# mcu0_primary.net
KiCad netlist of a schematic drawn in Altium Designer
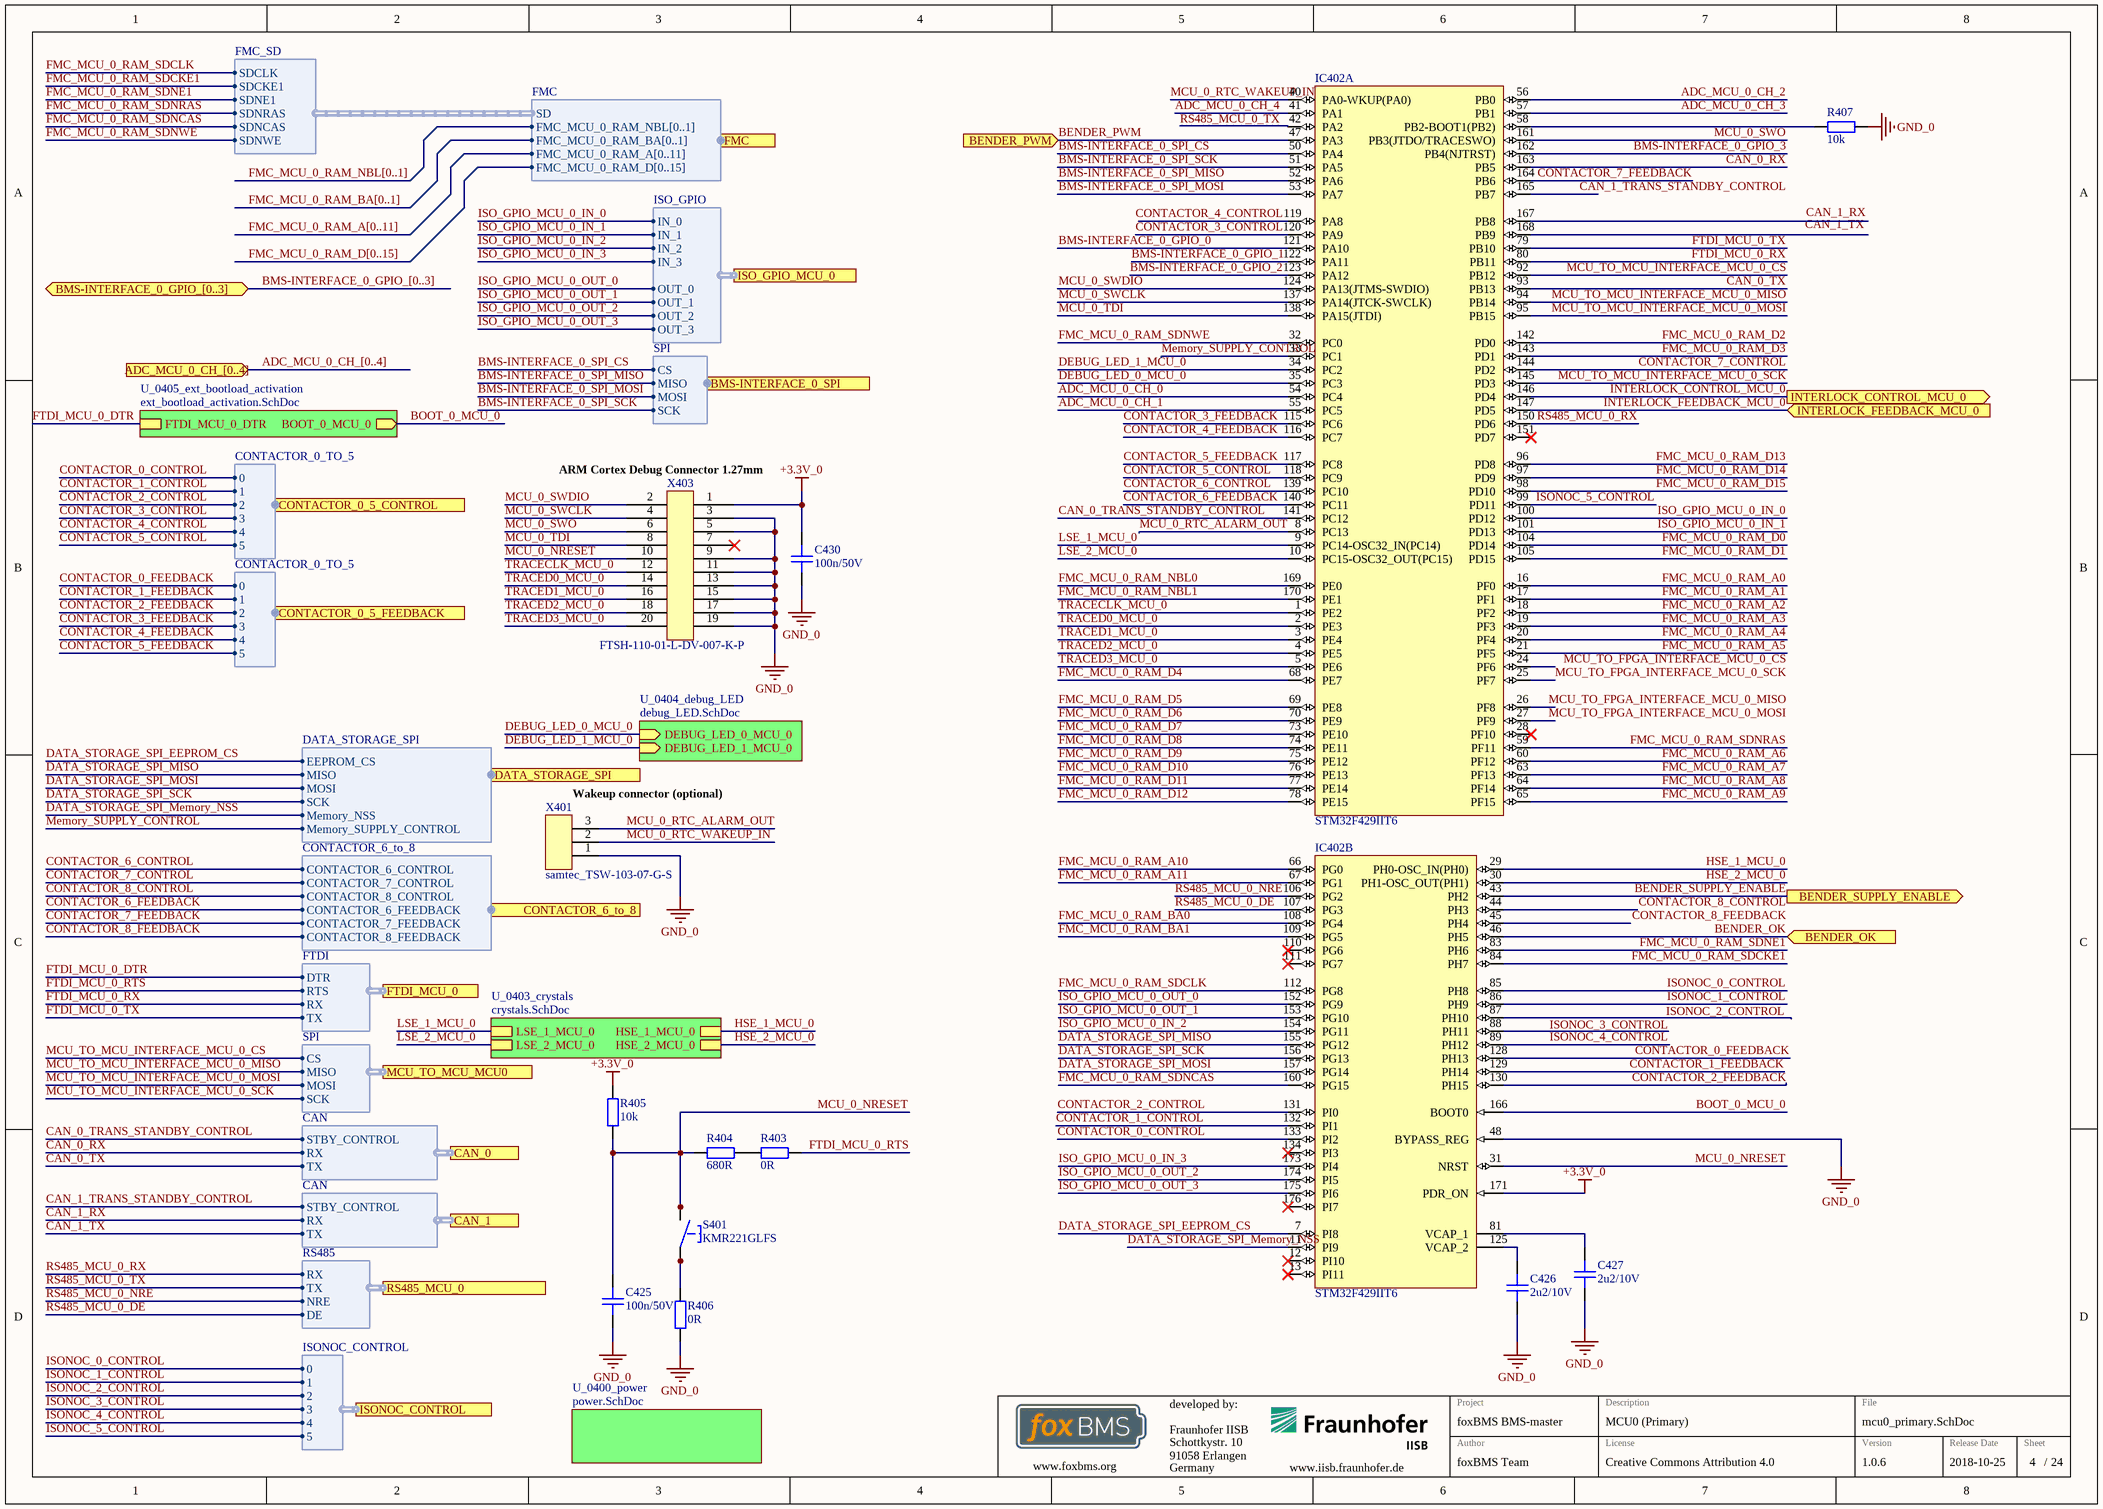
[diagram p0: mcu0_primary.SchDoc]

(export (version "E")
  (design (tool "Eeschema 10.0.6"))
  (components
    (comp (ref "C425")
      (value "100n/50V")
      (footprint "CAPC1608X08N")
      (description "MLCC")
      (fields (field (name "PART NUMBER") "gen_C_ceramic_100n_50V_X7R_0603"))
      (libsource (lib "OE750") (part "C"))
    )
    (comp (ref "C426")
      (value "2u2/10V")
      (footprint "CAPC1608X08N")
      (description "MLCC")
      (fields (field (name "PART NUMBER") "gen_C_ceramic_2u2_10V_X5R_0603"))
      (libsource (lib "OE750") (part "C"))
    )
    (comp (ref "C427")
      (value "2u2/10V")
      (footprint "CAPC1608X08N")
      (description "MLCC")
      (fields (field (name "PART NUMBER") "gen_C_ceramic_2u2_10V_X5R_0603"))
      (libsource (lib "OE750") (part "C"))
    )
    (comp (ref "C430")
      (value "100n/50V")
      (footprint "CAPC1608X08N")
      (description "MLCC")
      (fields (field (name "PART NUMBER") "gen_C_ceramic_100n_50V_X7R_0603"))
      (libsource (lib "OE750") (part "C"))
    )
    (comp (ref "IC402")
      (value "STM32F429IIT6")
      (footprint "STM-LQFP176_N")
      (fields (field (name "MANUFACTURER") "STMicroelectronics"))
      (libsource (lib "Altium Content Vault") (part "MC-ARM-STM32F4X9-SQ176"))
    )
    (comp (ref "R403")
      (value "0R")
      (footprint "RESC1608X05N")
      (description "SMD Resistor 0R 0603")
      (fields (field (name "PART NUMBER") "gen_R_0R_0603") (field (name "POWER") "0.1W"))
      (libsource (lib "OE750") (part "R"))
    )
    (comp (ref "R404")
      (value "680R")
      (footprint "RESC1608X05N")
      (description "SMD Resistor 680R 0603")
      (fields (field (name "PART NUMBER") "gen_R_680R_0603") (field (name "TOLERANCE") "1%"))
      (libsource (lib "OE750") (part "R"))
    )
    (comp (ref "R405")
      (value "10k")
      (footprint "RESC1608X05N")
      (description "SMD Resistor 10k 0603")
      (fields (field (name "PART NUMBER") "gen_R_10k_0603") (field (name "TOLERANCE") "1%"))
      (libsource (lib "OE750") (part "R"))
    )
    (comp (ref "R406")
      (value "0R")
      (footprint "RESC1608X05N")
      (description "SMD Resistor 0R 0603")
      (fields (field (name "PART NUMBER") "gen_R_0R_0603") (field (name "POWER") "0.1W"))
      (libsource (lib "OE750") (part "R"))
    )
    (comp (ref "R407")
      (value "10k")
      (footprint "RESC1608X05N")
      (description "SMD Resistor 10k 0603")
      (fields (field (name "PART NUMBER") "gen_R_10k_0603") (field (name "TOLERANCE") "1%"))
      (libsource (lib "OE750") (part "R"))
    )
    (comp (ref "S401")
      (value "KMR221GLFS")
      (footprint "KMR2_Series")
      (description "Microminiature Tactile Switch")
      (fields (field (name "MANUFACTURER") "CK Components"))
      (libsource (lib "OE750") (part "Switch_4_Pin"))
    )
    (comp (ref "X401")
      (value "samtec_TSW-103-07-G-S")
      (footprint "Pinheader_2.54_3")
      (description "Board-To-Board Connector, Vertical, 2.54 mm, 3 Contacts, Header, TSW Series, Through Hole, 1 Row")
      (fields (field (name "MANUFACTURER") "Samtec"))
      (libsource (lib "OE750") (part "X3"))
    )
    (comp (ref "X403")
      (value "FTSH-110-01-L-DV-007-K-P")
      (footprint "CORTEX_DEBUG_20_PIN")
      (description "Board-To-Board Connector, ARM Cortex Debug Header 20 Pin")
      (fields
        (field (name "PART NUMBER") "samtec_FTSH-110-01-L-DV-007-K-P")
        (field (name "MANUFACTURER") "Samtec")
      )
      (libsource (lib "OE750") (part "CORTEX_DEBUG_20_PIN"))
    )
  )
  (nets
    (net (code "12") (name "+3.3V_0") (class "Default")
      (node (ref "C430") (pin "1") (pinfunction "1_1") (pintype "passive"))
      (node (ref "IC402") (pin "171") (pinfunction "PDR_ON_171") (pintype "input"))
      (node (ref "R405") (pin "2") (pinfunction "2_2") (pintype "passive"))
      (node (ref "X403") (pin "1") (pintype "passive"))
    )
    (net (code "13") (name "/ADC_MCU_0_CH_0") (class "Default")
      (node (ref "IC402") (pin "54") (pinfunction "PC4_54") (pintype "bidirectional"))
    )
    (net (code "14") (name "/ADC_MCU_0_CH_1") (class "Default")
      (node (ref "IC402") (pin "55") (pinfunction "PC5_55") (pintype "bidirectional"))
    )
    (net (code "15") (name "/ADC_MCU_0_CH_2") (class "Default")
      (node (ref "IC402") (pin "56") (pinfunction "PB0_56") (pintype "bidirectional"))
    )
    (net (code "16") (name "/ADC_MCU_0_CH_3") (class "Default")
      (node (ref "IC402") (pin "57") (pinfunction "PB1_57") (pintype "bidirectional"))
    )
    (net (code "17") (name "/ADC_MCU_0_CH_4") (class "Default")
      (node (ref "IC402") (pin "41") (pinfunction "PA1_41") (pintype "bidirectional"))
    )
    (net (code "19") (name "/BENDER_OK") (class "Default")
      (node (ref "IC402") (pin "46") (pinfunction "PH5_46") (pintype "bidirectional"))
    )
    (net (code "20") (name "/BENDER_PWM") (class "Default")
      (node (ref "IC402") (pin "47") (pinfunction "PA3_47") (pintype "bidirectional"))
    )
    (net (code "21") (name "/BENDER_SUPPLY_ENABLE") (class "Default")
      (node (ref "IC402") (pin "43") (pinfunction "PH2_43") (pintype "bidirectional"))
    )
    (net (code "22") (name "/BMS-INTERFACE_0_GPIO_0") (class "Default")
      (node (ref "IC402") (pin "121") (pinfunction "PA10_121") (pintype "bidirectional"))
    )
    (net (code "23") (name "/BMS-INTERFACE_0_GPIO_1") (class "Default")
      (node (ref "IC402") (pin "122") (pinfunction "PA11_122") (pintype "bidirectional"))
    )
    (net (code "24") (name "/BMS-INTERFACE_0_GPIO_2") (class "Default")
      (node (ref "IC402") (pin "123") (pinfunction "PA12_123") (pintype "bidirectional"))
    )
    (net (code "25") (name "/BMS-INTERFACE_0_GPIO_3") (class "Default")
      (node (ref "IC402") (pin "162") (pinfunction "PB4(NJTRST)_162") (pintype "bidirectional"))
    )
    (net (code "27") (name "/BMS-INTERFACE_0_SPI_CS") (class "Default")
      (node (ref "IC402") (pin "50") (pinfunction "PA4_50") (pintype "bidirectional"))
    )
    (net (code "28") (name "/BMS-INTERFACE_0_SPI_MISO") (class "Default")
      (node (ref "IC402") (pin "52") (pinfunction "PA6_52") (pintype "bidirectional"))
    )
    (net (code "29") (name "/BMS-INTERFACE_0_SPI_MOSI") (class "Default")
      (node (ref "IC402") (pin "53") (pinfunction "PA7_53") (pintype "bidirectional"))
    )
    (net (code "30") (name "/BMS-INTERFACE_0_SPI_SCK") (class "Default")
      (node (ref "IC402") (pin "51") (pinfunction "PA5_51") (pintype "bidirectional"))
    )
    (net (code "31") (name "/BOOT_0_MCU_0") (class "Default")
      (node (ref "IC402") (pin "166") (pinfunction "BOOT0_166") (pintype "input"))
    )
    (net (code "32") (name "/CAN_0_RX") (class "Default")
      (node (ref "IC402") (pin "163") (pinfunction "PB5_163") (pintype "bidirectional"))
    )
    (net (code "33") (name "/CAN_0_TRANS_STANDBY_CONTROL") (class "Default")
      (node (ref "IC402") (pin "141") (pinfunction "PC12_141") (pintype "bidirectional"))
    )
    (net (code "34") (name "/CAN_0_TX") (class "Default")
      (node (ref "IC402") (pin "93") (pinfunction "PB13_93") (pintype "bidirectional"))
    )
    (net (code "38") (name "/CONTACTOR_0_CONTROL") (class "Default")
      (node (ref "IC402") (pin "133") (pinfunction "PI2_133") (pintype "bidirectional"))
    )
    (net (code "39") (name "/CONTACTOR_0_FEEDBACK") (class "Default")
      (node (ref "IC402") (pin "128") (pinfunction "PH13_128") (pintype "bidirectional"))
    )
    (net (code "40") (name "/CONTACTOR_1_CONTROL") (class "Default")
      (node (ref "IC402") (pin "132") (pinfunction "PI1_132") (pintype "bidirectional"))
    )
    (net (code "41") (name "/CONTACTOR_1_FEEDBACK") (class "Default")
      (node (ref "IC402") (pin "129") (pinfunction "PH14_129") (pintype "bidirectional"))
    )
    (net (code "42") (name "/CONTACTOR_2_CONTROL") (class "Default")
      (node (ref "IC402") (pin "131") (pinfunction "PI0_131") (pintype "bidirectional"))
    )
    (net (code "44") (name "/CONTACTOR_3_CONTROL") (class "Default")
      (node (ref "IC402") (pin "120") (pinfunction "PA9_120") (pintype "bidirectional"))
    )
    (net (code "45") (name "/CONTACTOR_3_FEEDBACK") (class "Default")
      (node (ref "IC402") (pin "115") (pinfunction "PC6_115") (pintype "bidirectional"))
    )
    (net (code "47") (name "/CONTACTOR_4_FEEDBACK") (class "Default")
      (node (ref "IC402") (pin "116") (pinfunction "PC7_116") (pintype "bidirectional"))
    )
    (net (code "48") (name "/CONTACTOR_5_CONTROL") (class "Default")
      (node (ref "IC402") (pin "118") (pinfunction "PC9_118") (pintype "bidirectional"))
    )
    (net (code "49") (name "/CONTACTOR_5_FEEDBACK") (class "Default")
      (node (ref "IC402") (pin "117") (pinfunction "PC8_117") (pintype "bidirectional"))
    )
    (net (code "50") (name "/CONTACTOR_6_CONTROL") (class "Default")
      (node (ref "IC402") (pin "139") (pinfunction "PC10_139") (pintype "bidirectional"))
    )
    (net (code "51") (name "/CONTACTOR_6_FEEDBACK") (class "Default")
      (node (ref "IC402") (pin "140") (pinfunction "PC11_140") (pintype "bidirectional"))
    )
    (net (code "52") (name "/CONTACTOR_7_CONTROL") (class "Default")
      (node (ref "IC402") (pin "144") (pinfunction "PD2_144") (pintype "bidirectional"))
    )
    (net (code "53") (name "/CONTACTOR_7_FEEDBACK") (class "Default")
      (node (ref "IC402") (pin "164") (pinfunction "PB6_164") (pintype "bidirectional"))
    )
    (net (code "56") (name "/DATA_STORAGE_SPI_EEPROM_CS") (class "Default")
      (node (ref "IC402") (pin "7") (pinfunction "PI8_7") (pintype "bidirectional"))
    )
    (net (code "57") (name "/DATA_STORAGE_SPI_MISO") (class "Default")
      (node (ref "IC402") (pin "155") (pinfunction "PG12_155") (pintype "bidirectional"))
    )
    (net (code "58") (name "/DATA_STORAGE_SPI_MOSI") (class "Default")
      (node (ref "IC402") (pin "157") (pinfunction "PG14_157") (pintype "bidirectional"))
    )
    (net (code "59") (name "/DATA_STORAGE_SPI_Memory_NSS") (class "Default")
      (node (ref "IC402") (pin "11") (pinfunction "PI9_11") (pintype "bidirectional"))
    )
    (net (code "60") (name "/DATA_STORAGE_SPI_SCK") (class "Default")
      (node (ref "IC402") (pin "156") (pinfunction "PG13_156") (pintype "bidirectional"))
    )
    (net (code "61") (name "/DEBUG_LED_0_MCU_0") (class "Default")
      (node (ref "IC402") (pin "35") (pinfunction "PC3_35") (pintype "bidirectional"))
    )
    (net (code "62") (name "/DEBUG_LED_1_MCU_0") (class "Default")
      (node (ref "IC402") (pin "34") (pinfunction "PC2_34") (pintype "bidirectional"))
    )
    (net (code "63") (name "/FMC_MCU_0_RAM_A0") (class "Default")
      (node (ref "IC402") (pin "16") (pinfunction "PF0_16") (pintype "bidirectional"))
    )
    (net (code "64") (name "/FMC_MCU_0_RAM_A1") (class "Default")
      (node (ref "IC402") (pin "17") (pinfunction "PF1_17") (pintype "bidirectional"))
    )
    (net (code "65") (name "/FMC_MCU_0_RAM_A2") (class "Default")
      (node (ref "IC402") (pin "18") (pinfunction "PF2_18") (pintype "bidirectional"))
    )
    (net (code "66") (name "/FMC_MCU_0_RAM_A3") (class "Default")
      (node (ref "IC402") (pin "19") (pinfunction "PF3_19") (pintype "bidirectional"))
    )
    (net (code "67") (name "/FMC_MCU_0_RAM_A4") (class "Default")
      (node (ref "IC402") (pin "20") (pinfunction "PF4_20") (pintype "bidirectional"))
    )
    (net (code "68") (name "/FMC_MCU_0_RAM_A5") (class "Default")
      (node (ref "IC402") (pin "21") (pinfunction "PF5_21") (pintype "bidirectional"))
    )
    (net (code "69") (name "/FMC_MCU_0_RAM_A6") (class "Default")
      (node (ref "IC402") (pin "60") (pinfunction "PF12_60") (pintype "bidirectional"))
    )
    (net (code "70") (name "/FMC_MCU_0_RAM_A7") (class "Default")
      (node (ref "IC402") (pin "63") (pinfunction "PF13_63") (pintype "bidirectional"))
    )
    (net (code "71") (name "/FMC_MCU_0_RAM_A8") (class "Default")
      (node (ref "IC402") (pin "64") (pinfunction "PF14_64") (pintype "bidirectional"))
    )
    (net (code "72") (name "/FMC_MCU_0_RAM_A9") (class "Default")
      (node (ref "IC402") (pin "65") (pinfunction "PF15_65") (pintype "bidirectional"))
    )
    (net (code "73") (name "/FMC_MCU_0_RAM_A10") (class "Default")
      (node (ref "IC402") (pin "66") (pinfunction "PG0_66") (pintype "bidirectional"))
    )
    (net (code "74") (name "/FMC_MCU_0_RAM_A11") (class "Default")
      (node (ref "IC402") (pin "67") (pinfunction "PG1_67") (pintype "bidirectional"))
    )
    (net (code "75") (name "/FMC_MCU_0_RAM_BA0") (class "Default")
      (node (ref "IC402") (pin "108") (pinfunction "PG4_108") (pintype "bidirectional"))
    )
    (net (code "76") (name "/FMC_MCU_0_RAM_BA1") (class "Default")
      (node (ref "IC402") (pin "109") (pinfunction "PG5_109") (pintype "bidirectional"))
    )
    (net (code "78") (name "/FMC_MCU_0_RAM_D0") (class "Default")
      (node (ref "IC402") (pin "104") (pinfunction "PD14_104") (pintype "bidirectional"))
    )
    (net (code "79") (name "/FMC_MCU_0_RAM_D1") (class "Default")
      (node (ref "IC402") (pin "105") (pinfunction "PD15_105") (pintype "bidirectional"))
    )
    (net (code "80") (name "/FMC_MCU_0_RAM_D2") (class "Default")
      (node (ref "IC402") (pin "142") (pinfunction "PD0_142") (pintype "bidirectional"))
    )
    (net (code "81") (name "/FMC_MCU_0_RAM_D3") (class "Default")
      (node (ref "IC402") (pin "143") (pinfunction "PD1_143") (pintype "bidirectional"))
    )
    (net (code "82") (name "/FMC_MCU_0_RAM_D4") (class "Default")
      (node (ref "IC402") (pin "68") (pinfunction "PE7_68") (pintype "bidirectional"))
    )
    (net (code "83") (name "/FMC_MCU_0_RAM_D5") (class "Default")
      (node (ref "IC402") (pin "69") (pinfunction "PE8_69") (pintype "bidirectional"))
    )
    (net (code "84") (name "/FMC_MCU_0_RAM_D6") (class "Default")
      (node (ref "IC402") (pin "70") (pinfunction "PE9_70") (pintype "bidirectional"))
    )
    (net (code "85") (name "/FMC_MCU_0_RAM_D7") (class "Default")
      (node (ref "IC402") (pin "73") (pinfunction "PE10_73") (pintype "bidirectional"))
    )
    (net (code "86") (name "/FMC_MCU_0_RAM_D8") (class "Default")
      (node (ref "IC402") (pin "74") (pinfunction "PE11_74") (pintype "bidirectional"))
    )
    (net (code "87") (name "/FMC_MCU_0_RAM_D9") (class "Default")
      (node (ref "IC402") (pin "75") (pinfunction "PE12_75") (pintype "bidirectional"))
    )
    (net (code "88") (name "/FMC_MCU_0_RAM_D10") (class "Default")
      (node (ref "IC402") (pin "76") (pinfunction "PE13_76") (pintype "bidirectional"))
    )
    (net (code "89") (name "/FMC_MCU_0_RAM_D11") (class "Default")
      (node (ref "IC402") (pin "77") (pinfunction "PE14_77") (pintype "bidirectional"))
    )
    (net (code "90") (name "/FMC_MCU_0_RAM_D12") (class "Default")
      (node (ref "IC402") (pin "78") (pinfunction "PE15_78") (pintype "bidirectional"))
    )
    (net (code "91") (name "/FMC_MCU_0_RAM_D13") (class "Default")
      (node (ref "IC402") (pin "96") (pinfunction "PD8_96") (pintype "bidirectional"))
    )
    (net (code "92") (name "/FMC_MCU_0_RAM_D14") (class "Default")
      (node (ref "IC402") (pin "97") (pinfunction "PD9_97") (pintype "bidirectional"))
    )
    (net (code "93") (name "/FMC_MCU_0_RAM_D15") (class "Default")
      (node (ref "IC402") (pin "98") (pinfunction "PD10_98") (pintype "bidirectional"))
    )
    (net (code "95") (name "/FMC_MCU_0_RAM_NBL0") (class "Default")
      (node (ref "IC402") (pin "169") (pinfunction "PE0_169") (pintype "bidirectional"))
    )
    (net (code "96") (name "/FMC_MCU_0_RAM_NBL1") (class "Default")
      (node (ref "IC402") (pin "170") (pinfunction "PE1_170") (pintype "bidirectional"))
    )
    (net (code "98") (name "/FMC_MCU_0_RAM_SDCKE1") (class "Default")
      (node (ref "IC402") (pin "84") (pinfunction "PH7_84") (pintype "bidirectional"))
    )
    (net (code "99") (name "/FMC_MCU_0_RAM_SDCLK") (class "Default")
      (node (ref "IC402") (pin "112") (pinfunction "PG8_112") (pintype "bidirectional"))
    )
    (net (code "100") (name "/FMC_MCU_0_RAM_SDNCAS") (class "Default")
      (node (ref "IC402") (pin "160") (pinfunction "PG15_160") (pintype "bidirectional"))
    )
    (net (code "101") (name "/FMC_MCU_0_RAM_SDNE1") (class "Default")
      (node (ref "IC402") (pin "83") (pinfunction "PH6_83") (pintype "bidirectional"))
    )
    (net (code "102") (name "/FMC_MCU_0_RAM_SDNRAS") (class "Default")
      (node (ref "IC402") (pin "59") (pinfunction "PF11_59") (pintype "bidirectional"))
    )
    (net (code "103") (name "/FMC_MCU_0_RAM_SDNWE") (class "Default")
      (node (ref "IC402") (pin "32") (pinfunction "PC0_32") (pintype "bidirectional"))
    )
    (net (code "106") (name "/FTDI_MCU_0_RTS") (class "Default")
      (node (ref "R403") (pin "2") (pinfunction "2_2") (pintype "passive"))
    )
    (net (code "107") (name "/FTDI_MCU_0_RX") (class "Default")
      (node (ref "IC402") (pin "80") (pinfunction "PB11_80") (pintype "bidirectional"))
    )
    (net (code "108") (name "/FTDI_MCU_0_TX") (class "Default")
      (node (ref "IC402") (pin "79") (pinfunction "PB10_79") (pintype "bidirectional"))
    )
    (net (code "109") (name "/HSE_1_MCU_0") (class "Default")
      (node (ref "IC402") (pin "29") (pinfunction "PH0-OSC_IN(PH0)_29") (pintype "bidirectional"))
    )
    (net (code "110") (name "/HSE_2_MCU_0") (class "Default")
      (node (ref "IC402") (pin "30") (pinfunction "PH1-OSC_OUT(PH1)_30") (pintype "bidirectional"))
    )
    (net (code "111") (name "/INTERLOCK_CONTROL_MCU_0") (class "Default")
      (node (ref "IC402") (pin "146") (pinfunction "PD4_146") (pintype "bidirectional"))
    )
    (net (code "112") (name "/INTERLOCK_FEEDBACK_MCU_0") (class "Default")
      (node (ref "IC402") (pin "147") (pinfunction "PD5_147") (pintype "bidirectional"))
    )
    (net (code "113") (name "/ISONOC_0_CONTROL") (class "Default")
      (node (ref "IC402") (pin "85") (pinfunction "PH8_85") (pintype "bidirectional"))
    )
    (net (code "114") (name "/ISONOC_1_CONTROL") (class "Default")
      (node (ref "IC402") (pin "86") (pinfunction "PH9_86") (pintype "bidirectional"))
    )
    (net (code "117") (name "/ISONOC_4_CONTROL") (class "Default")
      (node (ref "IC402") (pin "89") (pinfunction "PH12_89") (pintype "bidirectional"))
    )
    (net (code "118") (name "/ISONOC_5_CONTROL") (class "Default")
      (node (ref "IC402") (pin "99") (pinfunction "PD11_99") (pintype "bidirectional"))
    )
    (net (code "119") (name "/ISO_GPIO_MCU_0_IN_0") (class "Default")
      (node (ref "IC402") (pin "100") (pinfunction "PD12_100") (pintype "bidirectional"))
    )
    (net (code "120") (name "/ISO_GPIO_MCU_0_IN_1") (class "Default")
      (node (ref "IC402") (pin "101") (pinfunction "PD13_101") (pintype "bidirectional"))
    )
    (net (code "121") (name "/ISO_GPIO_MCU_0_IN_2") (class "Default")
      (node (ref "IC402") (pin "154") (pinfunction "PG11_154") (pintype "bidirectional"))
    )
    (net (code "122") (name "/ISO_GPIO_MCU_0_IN_3") (class "Default")
      (node (ref "IC402") (pin "173") (pinfunction "PI4_173") (pintype "bidirectional"))
    )
    (net (code "123") (name "/ISO_GPIO_MCU_0_OUT_0") (class "Default")
      (node (ref "IC402") (pin "152") (pinfunction "PG9_152") (pintype "bidirectional"))
    )
    (net (code "124") (name "/ISO_GPIO_MCU_0_OUT_1") (class "Default")
      (node (ref "IC402") (pin "153") (pinfunction "PG10_153") (pintype "bidirectional"))
    )
    (net (code "125") (name "/ISO_GPIO_MCU_0_OUT_2") (class "Default")
      (node (ref "IC402") (pin "174") (pinfunction "PI5_174") (pintype "bidirectional"))
    )
    (net (code "126") (name "/ISO_GPIO_MCU_0_OUT_3") (class "Default")
      (node (ref "IC402") (pin "175") (pinfunction "PI6_175") (pintype "bidirectional"))
    )
    (net (code "127") (name "/LSE_1_MCU_0") (class "Default")
      (node (ref "IC402") (pin "9") (pinfunction "PC14-OSC32_IN(PC14)_9") (pintype "bidirectional"))
    )
    (net (code "128") (name "/LSE_2_MCU_0") (class "Default")
      (node (ref "IC402") (pin "10") (pinfunction "PC15-OSC32_OUT(PC15)_10") (pintype "bidirectional"))
    )
    (net (code "129") (name "/MCU_0_NRESET") (class "Default")
      (node (ref "C425") (pin "1") (pinfunction "1_1") (pintype "passive"))
      (node (ref "IC402") (pin "31") (pinfunction "NRST_31") (pintype "bidirectional"))
      (node (ref "R404") (pin "1") (pinfunction "1_1") (pintype "passive"))
      (node (ref "R405") (pin "1") (pinfunction "1_1") (pintype "passive"))
      (node (ref "S401") (pin "3") (pintype "passive"))
      (node (ref "S401") (pin "4") (pintype "passive"))
      (node (ref "X403") (pin "10") (pintype "passive"))
    )
    (net (code "130") (name "/MCU_0_RTC_ALARM_OUT") (class "Default")
      (node (ref "IC402") (pin "8") (pinfunction "PC13_8") (pintype "bidirectional"))
      (node (ref "X401") (pin "3") (pintype "passive"))
    )
    (net (code "131") (name "/MCU_0_RTC_WAKEUP_IN") (class "Default")
      (node (ref "IC402") (pin "40") (pinfunction "PA0-WKUP(PA0)_40") (pintype "bidirectional"))
      (node (ref "X401") (pin "2") (pintype "passive"))
    )
    (net (code "132") (name "/MCU_0_SWCLK") (class "Default")
      (node (ref "IC402") (pin "137") (pinfunction "PA14(JTCK-SWCLK)_137") (pintype "bidirectional"))
      (node (ref "X403") (pin "4") (pintype "passive"))
    )
    (net (code "133") (name "/MCU_0_SWDIO") (class "Default")
      (node (ref "IC402") (pin "124") (pinfunction "PA13(JTMS-SWDIO)_124") (pintype "bidirectional"))
      (node (ref "X403") (pin "2") (pintype "passive"))
    )
    (net (code "134") (name "/MCU_0_SWO") (class "Default")
      (node (ref "IC402") (pin "161") (pinfunction "PB3(JTDO/TRACESWO)_161") (pintype "bidirectional"))
      (node (ref "X403") (pin "6") (pintype "passive"))
    )
    (net (code "135") (name "/MCU_0_TDI") (class "Default")
      (node (ref "IC402") (pin "138") (pinfunction "PA15(JTDI)_138") (pintype "bidirectional"))
      (node (ref "X403") (pin "8") (pintype "passive"))
    )
    (net (code "140") (name "/MCU_TO_MCU_INTERFACE_MCU_0_CS") (class "Default")
      (node (ref "IC402") (pin "92") (pinfunction "PB12_92") (pintype "bidirectional"))
    )
    (net (code "141") (name "/MCU_TO_MCU_INTERFACE_MCU_0_MISO") (class "Default")
      (node (ref "IC402") (pin "94") (pinfunction "PB14_94") (pintype "bidirectional"))
    )
    (net (code "142") (name "/MCU_TO_MCU_INTERFACE_MCU_0_MOSI") (class "Default")
      (node (ref "IC402") (pin "95") (pinfunction "PB15_95") (pintype "bidirectional"))
    )
    (net (code "143") (name "/MCU_TO_MCU_INTERFACE_MCU_0_SCK") (class "Default")
      (node (ref "IC402") (pin "145") (pinfunction "PD3_145") (pintype "bidirectional"))
    )
    (net (code "144") (name "/Memory_SUPPLY_CONTROL") (class "Default")
      (node (ref "IC402") (pin "33") (pinfunction "PC1_33") (pintype "bidirectional"))
    )
    (net (code "145") (name "/RS485_MCU_0_DE") (class "Default")
      (node (ref "IC402") (pin "107") (pinfunction "PG3_107") (pintype "bidirectional"))
    )
    (net (code "146") (name "/RS485_MCU_0_NRE") (class "Default")
      (node (ref "IC402") (pin "106") (pinfunction "PG2_106") (pintype "bidirectional"))
    )
    (net (code "147") (name "/RS485_MCU_0_RX") (class "Default")
      (node (ref "IC402") (pin "150") (pinfunction "PD6_150") (pintype "bidirectional"))
    )
    (net (code "149") (name "/TRACECLK_MCU_0") (class "Default")
      (node (ref "IC402") (pin "1") (pinfunction "PE2_1") (pintype "bidirectional"))
      (node (ref "X403") (pin "12") (pintype "passive"))
    )
    (net (code "150") (name "/TRACED0_MCU_0") (class "Default")
      (node (ref "IC402") (pin "2") (pinfunction "PE3_2") (pintype "bidirectional"))
      (node (ref "X403") (pin "14") (pintype "passive"))
    )
    (net (code "151") (name "/TRACED1_MCU_0") (class "Default")
      (node (ref "IC402") (pin "3") (pinfunction "PE4_3") (pintype "bidirectional"))
      (node (ref "X403") (pin "16") (pintype "passive"))
    )
    (net (code "152") (name "/TRACED2_MCU_0") (class "Default")
      (node (ref "IC402") (pin "4") (pinfunction "PE5_4") (pintype "bidirectional"))
      (node (ref "X403") (pin "18") (pintype "passive"))
    )
    (net (code "153") (name "/TRACED3_MCU_0") (class "Default")
      (node (ref "IC402") (pin "5") (pinfunction "PE6_5") (pintype "bidirectional"))
      (node (ref "X403") (pin "20") (pintype "passive"))
    )
    (net (code "165") (name "GND_0") (class "Default")
      (node (ref "C425") (pin "2") (pinfunction "2_2") (pintype "passive"))
      (node (ref "C426") (pin "2") (pinfunction "2_2") (pintype "passive"))
      (node (ref "C427") (pin "2") (pinfunction "2_2") (pintype "passive"))
      (node (ref "C430") (pin "2") (pinfunction "2_2") (pintype "passive"))
      (node (ref "IC402") (pin "48") (pinfunction "BYPASS_REG_48") (pintype "input"))
      (node (ref "R406") (pin "1") (pinfunction "1_1") (pintype "passive"))
      (node (ref "R407") (pin "1") (pinfunction "1_1") (pintype "passive"))
      (node (ref "X401") (pin "1") (pintype "passive"))
      (node (ref "X403") (pin "11") (pintype "passive"))
      (node (ref "X403") (pin "13") (pintype "passive"))
      (node (ref "X403") (pin "15") (pintype "passive"))
      (node (ref "X403") (pin "17") (pintype "passive"))
      (node (ref "X403") (pin "19") (pintype "passive"))
      (node (ref "X403") (pin "3") (pintype "passive"))
      (node (ref "X403") (pin "5") (pintype "passive"))
      (node (ref "X403") (pin "9") (pintype "passive"))
    )
    (net (code "166") (name "Net-(IC402A-PB2-BOOT1(PB2))") (class "Default")
      (node (ref "IC402") (pin "58") (pinfunction "PB2-BOOT1(PB2)_58") (pintype "bidirectional"))
      (node (ref "R407") (pin "2") (pinfunction "2_2") (pintype "passive"))
    )
    (net (code "167") (name "Net-(IC402B-VCAP_1)") (class "Default")
      (node (ref "C427") (pin "1") (pinfunction "1_1") (pintype "passive"))
      (node (ref "IC402") (pin "81") (pinfunction "VCAP_1_81") (pintype "power_in"))
    )
    (net (code "168") (name "Net-(IC402B-VCAP_2)") (class "Default")
      (node (ref "C426") (pin "1") (pinfunction "1_1") (pintype "passive"))
      (node (ref "IC402") (pin "125") (pinfunction "VCAP_2_125") (pintype "power_in"))
    )
    (net (code "169") (name "Net-(R403-Pad1)") (class "Default")
      (node (ref "R403") (pin "1") (pinfunction "1_1") (pintype "passive"))
      (node (ref "R404") (pin "2") (pinfunction "2_2") (pintype "passive"))
    )
    (net (code "170") (name "Net-(R406-Pad2)") (class "Default")
      (node (ref "R406") (pin "2") (pinfunction "2_2") (pintype "passive"))
      (node (ref "S401") (pin "1") (pintype "passive"))
      (node (ref "S401") (pin "2") (pintype "passive"))
    )
    (net (code "171") (name "unconnected-(IC402A-PA2-Pad42)") (class "Default")
      (node (ref "IC402") (pin "42") (pinfunction "PA2_42") (pintype "bidirectional"))
    )
    (net (code "172") (name "unconnected-(IC402A-PA8-Pad119)") (class "Default")
      (node (ref "IC402") (pin "119") (pinfunction "PA8_119") (pintype "bidirectional"))
    )
    (net (code "173") (name "unconnected-(IC402A-PB7-Pad165)") (class "Default")
      (node (ref "IC402") (pin "165") (pinfunction "PB7_165") (pintype "bidirectional"))
    )
    (net (code "174") (name "unconnected-(IC402A-PB8-Pad167)") (class "Default")
      (node (ref "IC402") (pin "167") (pinfunction "PB8_167") (pintype "bidirectional"))
    )
    (net (code "175") (name "unconnected-(IC402A-PB9-Pad168)") (class "Default")
      (node (ref "IC402") (pin "168") (pinfunction "PB9_168") (pintype "bidirectional"))
    )
    (net (code "176") (name "unconnected-(IC402A-PD7-Pad151)") (class "Default")
      (node (ref "IC402") (pin "151") (pinfunction "PD7_151") (pintype "bidirectional+no_connect"))
    )
    (net (code "177") (name "unconnected-(IC402A-PF6-Pad24)") (class "Default")
      (node (ref "IC402") (pin "24") (pinfunction "PF6_24") (pintype "bidirectional"))
    )
    (net (code "178") (name "unconnected-(IC402A-PF7-Pad25)") (class "Default")
      (node (ref "IC402") (pin "25") (pinfunction "PF7_25") (pintype "bidirectional"))
    )
    (net (code "179") (name "unconnected-(IC402A-PF8-Pad26)") (class "Default")
      (node (ref "IC402") (pin "26") (pinfunction "PF8_26") (pintype "bidirectional"))
    )
    (net (code "180") (name "unconnected-(IC402A-PF9-Pad27)") (class "Default")
      (node (ref "IC402") (pin "27") (pinfunction "PF9_27") (pintype "bidirectional"))
    )
    (net (code "181") (name "unconnected-(IC402A-PF10-Pad28)") (class "Default")
      (node (ref "IC402") (pin "28") (pinfunction "PF10_28") (pintype "bidirectional+no_connect"))
    )
    (net (code "182") (name "unconnected-(IC402B-PG6-Pad110)") (class "Default")
      (node (ref "IC402") (pin "110") (pinfunction "PG6_110") (pintype "bidirectional+no_connect"))
    )
    (net (code "183") (name "unconnected-(IC402B-PG7-Pad111)") (class "Default")
      (node (ref "IC402") (pin "111") (pinfunction "PG7_111") (pintype "bidirectional+no_connect"))
    )
    (net (code "184") (name "unconnected-(IC402B-PH3-Pad44)") (class "Default")
      (node (ref "IC402") (pin "44") (pinfunction "PH3_44") (pintype "bidirectional"))
    )
    (net (code "185") (name "unconnected-(IC402B-PH4-Pad45)") (class "Default")
      (node (ref "IC402") (pin "45") (pinfunction "PH4_45") (pintype "bidirectional"))
    )
    (net (code "186") (name "unconnected-(IC402B-PH10-Pad87)") (class "Default")
      (node (ref "IC402") (pin "87") (pinfunction "PH10_87") (pintype "bidirectional"))
    )
    (net (code "187") (name "unconnected-(IC402B-PH11-Pad88)") (class "Default")
      (node (ref "IC402") (pin "88") (pinfunction "PH11_88") (pintype "bidirectional"))
    )
    (net (code "188") (name "unconnected-(IC402B-PH15-Pad130)") (class "Default")
      (node (ref "IC402") (pin "130") (pinfunction "PH15_130") (pintype "bidirectional"))
    )
    (net (code "189") (name "unconnected-(IC402B-PI3-Pad134)") (class "Default")
      (node (ref "IC402") (pin "134") (pinfunction "PI3_134") (pintype "bidirectional+no_connect"))
    )
    (net (code "190") (name "unconnected-(IC402B-PI7-Pad176)") (class "Default")
      (node (ref "IC402") (pin "176") (pinfunction "PI7_176") (pintype "bidirectional+no_connect"))
    )
    (net (code "191") (name "unconnected-(IC402B-PI10-Pad12)") (class "Default")
      (node (ref "IC402") (pin "12") (pinfunction "PI10_12") (pintype "bidirectional+no_connect"))
    )
    (net (code "192") (name "unconnected-(IC402B-PI11-Pad13)") (class "Default")
      (node (ref "IC402") (pin "13") (pinfunction "PI11_13") (pintype "bidirectional+no_connect"))
    )
    (net (code "193") (name "unconnected-(X403-Pad7)") (class "Default")
      (node (ref "X403") (pin "7") (pintype "passive+no_connect"))
    )
  )
)
